# afron_atmega328_chassis.net
KiCad netlist of a schematic drawn in EAGLE
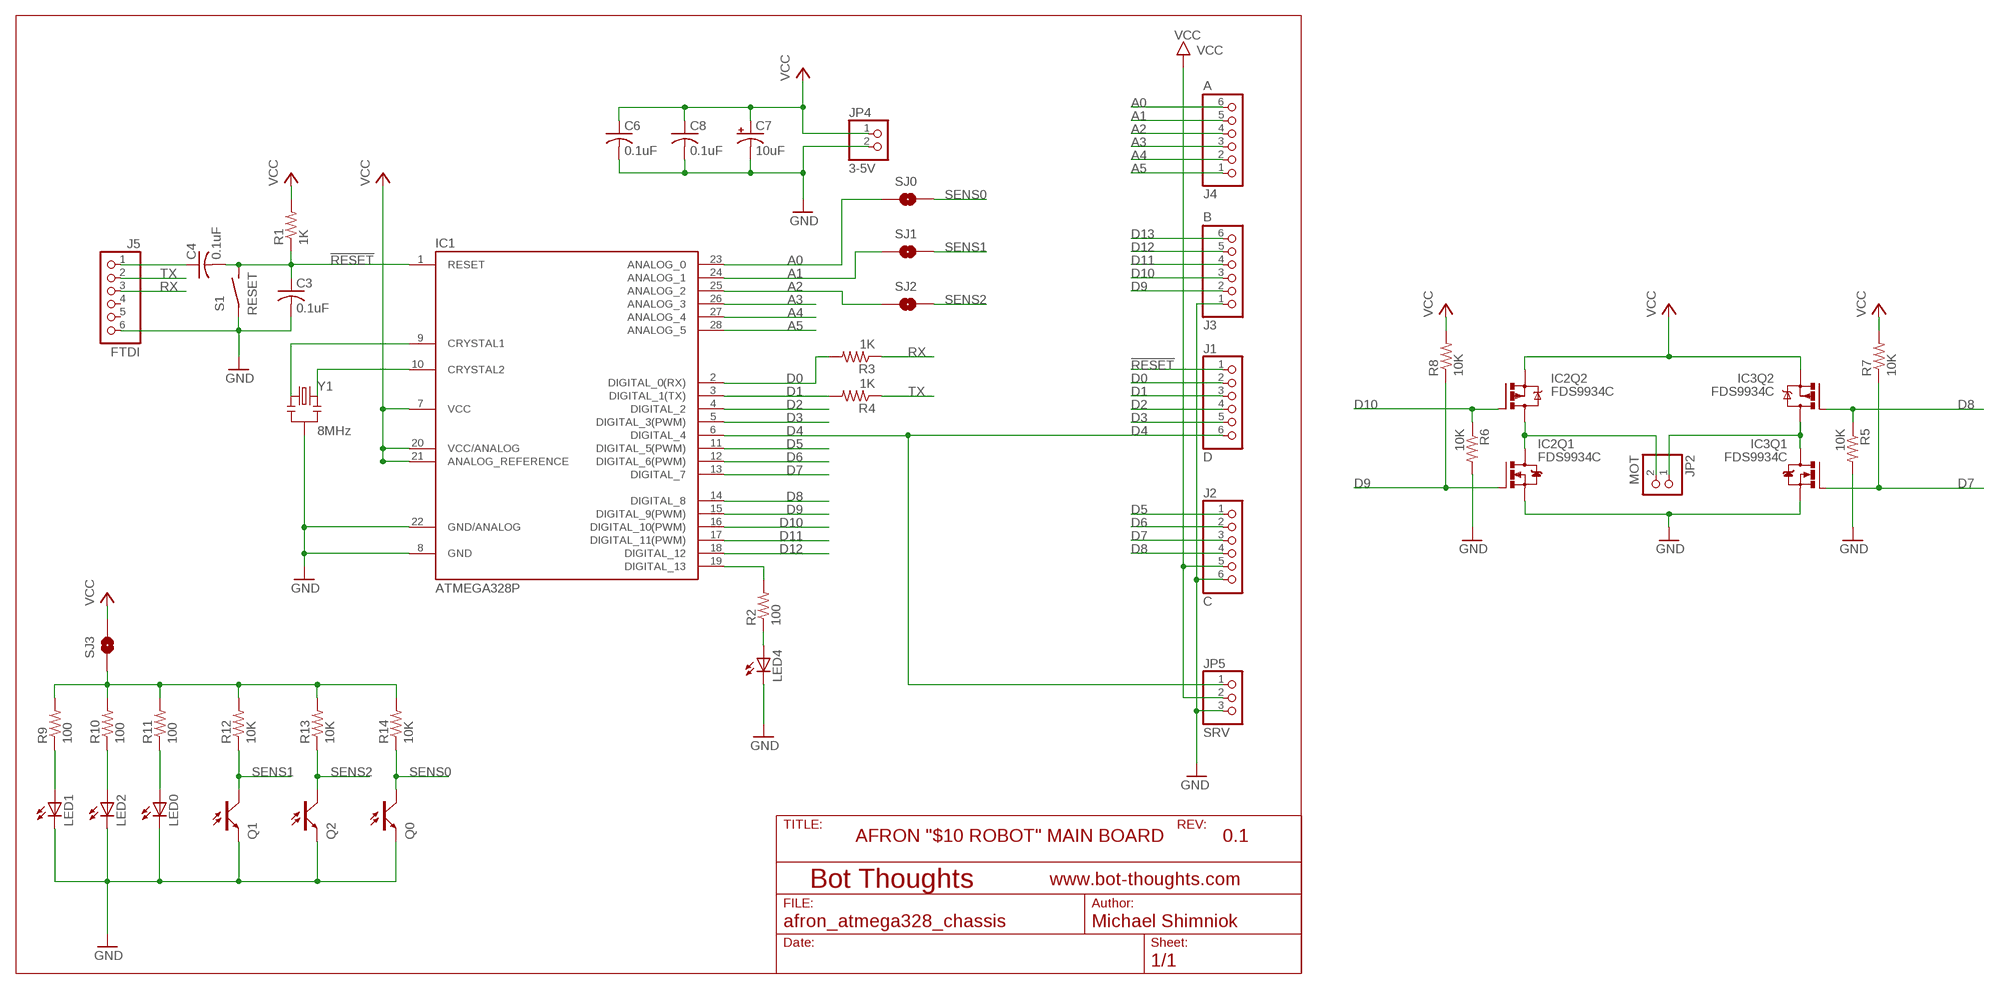
[diagram p0: schematic, sheet 1]

(export (version "E")
  (design (tool "Eeschema 10.0.6"))
  (components
    (comp (ref "C3")
      (value "0.1uF")
      (footprint "eagle-import:C050-024X044")
      (libsource (lib "eagle-import") (part "C-US050-024X044"))
    )
    (comp (ref "C4")
      (value "0.1uF")
      (footprint "eagle-import:C050-024X044")
      (libsource (lib "eagle-import") (part "C-US050-024X044"))
    )
    (comp (ref "C6")
      (value "0.1uF")
      (footprint "eagle-import:C050-024X044")
      (libsource (lib "eagle-import") (part "C-US050-024X044"))
    )
    (comp (ref "C7")
      (value "10uF")
      (footprint "eagle-import:E2,5-6")
      (libsource (lib "eagle-import") (part "CPOL-USE2.5-6"))
    )
    (comp (ref "C8")
      (value "0.1uF")
      (footprint "eagle-import:C050-024X044")
      (libsource (lib "eagle-import") (part "C-US050-024X044"))
    )
    (comp (ref "IC1")
      (value "ATMEGA328P")
      (footprint "eagle-import:DIL28-3")
      (libsource (lib "eagle-import") (part "ATMEGA168-PU"))
    )
    (comp (ref "IC2")
      (value "FDS9934C")
      (footprint "eagle-import:SOIC8")
      (libsource (lib "eagle-import") (part "FDS9934C"))
    )
    (comp (ref "IC3")
      (value "FDS9934C")
      (footprint "eagle-import:SOIC8")
      (libsource (lib "eagle-import") (part "FDS9934C"))
    )
    (comp (ref "J1")
      (value "D")
      (footprint "eagle-import:1X06-S")
      (libsource (lib "eagle-import") (part "PINHD-1X06_2.54-S"))
    )
    (comp (ref "J2")
      (value "C")
      (footprint "eagle-import:1X06-S")
      (libsource (lib "eagle-import") (part "PINHD-1X06_2.54-S"))
    )
    (comp (ref "J3")
      (value "B")
      (footprint "eagle-import:1X06-S")
      (libsource (lib "eagle-import") (part "PINHD-1X06_2.54-S"))
    )
    (comp (ref "J4")
      (value "A")
      (footprint "eagle-import:1X06-S")
      (libsource (lib "eagle-import") (part "PINHD-1X06_2.54-S"))
    )
    (comp (ref "J5")
      (value "FTDI")
      (footprint "eagle-import:1X06-S")
      (libsource (lib "eagle-import") (part "PINHD-1X06_2.54-S"))
    )
    (comp (ref "JP2")
      (value "MOT")
      (footprint "eagle-import:1X02-S")
      (libsource (lib "eagle-import") (part "PINHD-1X02_2.54-S"))
    )
    (comp (ref "JP4")
      (value "3-5V")
      (footprint "eagle-import:1X02-S")
      (libsource (lib "eagle-import") (part "PINHD-1X02_2.54-S"))
    )
    (comp (ref "JP5")
      (value "SRV")
      (footprint "eagle-import:1X03-S")
      (libsource (lib "eagle-import") (part "PINHD-1X03_2.54-S"))
    )
    (comp (ref "LED0")
      (value "LED3MM")
      (footprint "eagle-import:LED3MM")
      (libsource (lib "eagle-import") (part "LED3MM"))
    )
    (comp (ref "LED1")
      (value "LED3MM")
      (footprint "eagle-import:LED3MM")
      (libsource (lib "eagle-import") (part "LED3MM"))
    )
    (comp (ref "LED2")
      (value "LED3MM")
      (footprint "eagle-import:LED3MM")
      (libsource (lib "eagle-import") (part "LED3MM"))
    )
    (comp (ref "LED4")
      (value "LED3MM")
      (footprint "eagle-import:LED3MM")
      (libsource (lib "eagle-import") (part "LED3MM"))
    )
    (comp (ref "Q0")
      (value "PHOTOTRANSISTOR3MM")
      (footprint "eagle-import:LED3MM")
      (libsource (lib "eagle-import") (part "PHOTOTRANSISTOR3MM"))
    )
    (comp (ref "Q1")
      (value "PHOTOTRANSISTOR3MM")
      (footprint "eagle-import:LED3MM")
      (libsource (lib "eagle-import") (part "PHOTOTRANSISTOR3MM"))
    )
    (comp (ref "Q2")
      (value "PHOTOTRANSISTOR3MM")
      (footprint "eagle-import:LED3MM")
      (libsource (lib "eagle-import") (part "PHOTOTRANSISTOR3MM"))
    )
    (comp (ref "R1")
      (value "1K")
      (footprint "eagle-import:0204_5")
      (libsource (lib "eagle-import") (part "R-US_0204/5"))
    )
    (comp (ref "R2")
      (value "100")
      (footprint "eagle-import:0204_5")
      (libsource (lib "eagle-import") (part "R-US_0204/5"))
    )
    (comp (ref "R3")
      (value "1K")
      (footprint "eagle-import:0204_5")
      (libsource (lib "eagle-import") (part "R-US_0204/5"))
    )
    (comp (ref "R4")
      (value "1K")
      (footprint "eagle-import:0204_5")
      (libsource (lib "eagle-import") (part "R-US_0204/5"))
    )
    (comp (ref "R5")
      (value "10K")
      (footprint "eagle-import:0204_5")
      (libsource (lib "eagle-import") (part "R-US_0204/5"))
    )
    (comp (ref "R6")
      (value "10K")
      (footprint "eagle-import:0204_5")
      (libsource (lib "eagle-import") (part "R-US_0204/5"))
    )
    (comp (ref "R7")
      (value "10K")
      (footprint "eagle-import:0204_5")
      (libsource (lib "eagle-import") (part "R-US_0204/5"))
    )
    (comp (ref "R8")
      (value "10K")
      (footprint "eagle-import:0204_5")
      (libsource (lib "eagle-import") (part "R-US_0204/5"))
    )
    (comp (ref "R9")
      (value "100")
      (footprint "eagle-import:0204_5")
      (libsource (lib "eagle-import") (part "R-US_0204/5"))
    )
    (comp (ref "R10")
      (value "100")
      (footprint "eagle-import:0204_5")
      (libsource (lib "eagle-import") (part "R-US_0204/5"))
    )
    (comp (ref "R11")
      (value "100")
      (footprint "eagle-import:0204_5")
      (libsource (lib "eagle-import") (part "R-US_0204/5"))
    )
    (comp (ref "R12")
      (value "10K")
      (footprint "eagle-import:0204_5")
      (libsource (lib "eagle-import") (part "R-US_0204/5"))
    )
    (comp (ref "R13")
      (value "10K")
      (footprint "eagle-import:0204_5")
      (libsource (lib "eagle-import") (part "R-US_0204/5"))
    )
    (comp (ref "R14")
      (value "10K")
      (footprint "eagle-import:0204_5")
      (libsource (lib "eagle-import") (part "R-US_0204/5"))
    )
    (comp (ref "S1")
      (value "RESET")
      (footprint "eagle-import:6MMTACTILE")
      (libsource (lib "eagle-import") (part "SPST_TACT2"))
    )
    (comp (ref "SJ0")
      (value "SOLDERJUMPERTRACE")
      (footprint "eagle-import:SJ_2S-TRACE")
      (libsource (lib "eagle-import") (part "SOLDERJUMPERTRACE"))
    )
    (comp (ref "SJ1")
      (value "SOLDERJUMPERTRACE")
      (footprint "eagle-import:SJ_2S-TRACE")
      (libsource (lib "eagle-import") (part "SOLDERJUMPERTRACE"))
    )
    (comp (ref "SJ2")
      (value "SOLDERJUMPERTRACE")
      (footprint "eagle-import:SJ_2S-TRACE")
      (libsource (lib "eagle-import") (part "SOLDERJUMPERTRACE"))
    )
    (comp (ref "SJ3")
      (value "SOLDERJUMPERTRACE")
      (footprint "eagle-import:SJ_2S-TRACE")
      (libsource (lib "eagle-import") (part "SOLDERJUMPERTRACE"))
    )
    (comp (ref "Y1")
      (value "8MHz")
      (footprint "eagle-import:RESONATOR-PTH")
      (libsource (lib "eagle-import") (part "RESONATORPTH"))
    )
  )
  (nets
    (net (code "1") (name "/A0") (class "Default")
      (node (ref "IC1") (pin "23") (pinfunction "ANALOG_0_23") (pintype "bidirectional"))
      (node (ref "J4") (pin "6") (pinfunction "6_6") (pintype "passive"))
      (node (ref "SJ0") (pin "1") (pinfunction "1_1") (pintype "passive"))
    )
    (net (code "2") (name "/A1") (class "Default")
      (node (ref "IC1") (pin "24") (pinfunction "ANALOG_1_24") (pintype "bidirectional"))
      (node (ref "J4") (pin "5") (pinfunction "5_5") (pintype "passive"))
      (node (ref "SJ1") (pin "1") (pinfunction "1_1") (pintype "passive"))
    )
    (net (code "3") (name "/A2") (class "Default")
      (node (ref "IC1") (pin "25") (pinfunction "ANALOG_2_25") (pintype "bidirectional"))
      (node (ref "J4") (pin "4") (pinfunction "4_4") (pintype "passive"))
      (node (ref "SJ2") (pin "1") (pinfunction "1_1") (pintype "passive"))
    )
    (net (code "4") (name "/A3") (class "Default")
      (node (ref "IC1") (pin "26") (pinfunction "ANALOG_3_26") (pintype "bidirectional"))
      (node (ref "J4") (pin "3") (pinfunction "3_3") (pintype "passive"))
    )
    (net (code "5") (name "/A4") (class "Default")
      (node (ref "IC1") (pin "27") (pinfunction "ANALOG_4_27") (pintype "bidirectional"))
      (node (ref "J4") (pin "2") (pinfunction "2_2") (pintype "passive"))
    )
    (net (code "6") (name "/A5") (class "Default")
      (node (ref "IC1") (pin "28") (pinfunction "ANALOG_5_28") (pintype "bidirectional"))
      (node (ref "J4") (pin "1") (pinfunction "1_1") (pintype "passive"))
    )
    (net (code "7") (name "/D0") (class "Default")
      (node (ref "IC1") (pin "2") (pinfunction "DIGITAL_0(RX)_2") (pintype "bidirectional"))
      (node (ref "J1") (pin "2") (pinfunction "2_2") (pintype "passive"))
      (node (ref "R3") (pin "2") (pinfunction "2_2") (pintype "passive"))
    )
    (net (code "8") (name "/D1") (class "Default")
      (node (ref "IC1") (pin "3") (pinfunction "DIGITAL_1(TX)_3") (pintype "bidirectional"))
      (node (ref "J1") (pin "3") (pinfunction "3_3") (pintype "passive"))
      (node (ref "R4") (pin "2") (pinfunction "2_2") (pintype "passive"))
    )
    (net (code "9") (name "/D2") (class "Default")
      (node (ref "IC1") (pin "4") (pinfunction "DIGITAL_2_4") (pintype "bidirectional"))
      (node (ref "J1") (pin "4") (pinfunction "4_4") (pintype "passive"))
    )
    (net (code "10") (name "/D3") (class "Default")
      (node (ref "IC1") (pin "5") (pinfunction "DIGITAL_3(PWM)_5") (pintype "bidirectional"))
      (node (ref "J1") (pin "5") (pinfunction "5_5") (pintype "passive"))
    )
    (net (code "11") (name "/D4") (class "Default")
      (node (ref "IC1") (pin "6") (pinfunction "DIGITAL_4_6") (pintype "bidirectional"))
      (node (ref "J1") (pin "6") (pinfunction "6_6") (pintype "passive"))
      (node (ref "JP5") (pin "1") (pinfunction "1_1") (pintype "passive"))
    )
    (net (code "12") (name "/D5") (class "Default")
      (node (ref "IC1") (pin "11") (pinfunction "DIGITAL_5(PWM)_11") (pintype "bidirectional"))
      (node (ref "J2") (pin "1") (pinfunction "1_1") (pintype "passive"))
    )
    (net (code "13") (name "/D6") (class "Default")
      (node (ref "IC1") (pin "12") (pinfunction "DIGITAL_6(PWM)_12") (pintype "bidirectional"))
      (node (ref "J2") (pin "2") (pinfunction "2_2") (pintype "passive"))
    )
    (net (code "14") (name "/D7") (class "Default")
      (node (ref "IC1") (pin "13") (pinfunction "DIGITAL_7_13") (pintype "bidirectional"))
      (node (ref "IC3") (pin "2") (pinfunction "G_2") (pintype "passive"))
      (node (ref "J2") (pin "3") (pinfunction "3_3") (pintype "passive"))
      (node (ref "R7") (pin "1") (pinfunction "1_1") (pintype "passive"))
    )
    (net (code "15") (name "/D8") (class "Default")
      (node (ref "IC1") (pin "14") (pinfunction "DIGITAL_8_14") (pintype "bidirectional"))
      (node (ref "IC3") (pin "4") (pinfunction "G_4") (pintype "passive"))
      (node (ref "J2") (pin "4") (pinfunction "4_4") (pintype "passive"))
      (node (ref "R5") (pin "1") (pinfunction "1_1") (pintype "passive"))
    )
    (net (code "16") (name "/D9") (class "Default")
      (node (ref "IC1") (pin "15") (pinfunction "DIGITAL_9(PWM)_15") (pintype "bidirectional"))
      (node (ref "IC2") (pin "2") (pinfunction "G_2") (pintype "passive"))
      (node (ref "J3") (pin "2") (pinfunction "2_2") (pintype "passive"))
      (node (ref "R8") (pin "1") (pinfunction "1_1") (pintype "passive"))
    )
    (net (code "17") (name "/D10") (class "Default")
      (node (ref "IC1") (pin "16") (pinfunction "DIGITAL_10(PWM)_16") (pintype "bidirectional"))
      (node (ref "IC2") (pin "4") (pinfunction "G_4") (pintype "passive"))
      (node (ref "J3") (pin "3") (pinfunction "3_3") (pintype "passive"))
      (node (ref "R6") (pin "1") (pinfunction "1_1") (pintype "passive"))
    )
    (net (code "18") (name "/D11") (class "Default")
      (node (ref "IC1") (pin "17") (pinfunction "DIGITAL_11(PWM)_17") (pintype "bidirectional"))
      (node (ref "J3") (pin "4") (pinfunction "4_4") (pintype "passive"))
    )
    (net (code "19") (name "/D12") (class "Default")
      (node (ref "IC1") (pin "18") (pinfunction "DIGITAL_12_18") (pintype "bidirectional"))
      (node (ref "J3") (pin "5") (pinfunction "5_5") (pintype "passive"))
    )
    (net (code "20") (name "/D13") (class "Default")
      (node (ref "IC1") (pin "19") (pinfunction "DIGITAL_13_19") (pintype "bidirectional"))
      (node (ref "J3") (pin "6") (pinfunction "6_6") (pintype "passive"))
      (node (ref "R2") (pin "2") (pinfunction "2_2") (pintype "passive"))
    )
    (net (code "21") (name "/RX") (class "Default")
      (node (ref "J5") (pin "3") (pinfunction "3_3") (pintype "passive"))
      (node (ref "R3") (pin "1") (pinfunction "1_1") (pintype "passive"))
    )
    (net (code "22") (name "/SENS0") (class "Default")
      (node (ref "Q0") (pin "A") (pinfunction "A_A") (pintype "passive"))
      (node (ref "R14") (pin "1") (pinfunction "1_1") (pintype "passive"))
      (node (ref "SJ0") (pin "2") (pinfunction "2_2") (pintype "passive"))
    )
    (net (code "23") (name "/SENS1") (class "Default")
      (node (ref "Q1") (pin "A") (pinfunction "A_A") (pintype "passive"))
      (node (ref "R12") (pin "1") (pinfunction "1_1") (pintype "passive"))
      (node (ref "SJ1") (pin "2") (pinfunction "2_2") (pintype "passive"))
    )
    (net (code "24") (name "/SENS2") (class "Default")
      (node (ref "Q2") (pin "A") (pinfunction "A_A") (pintype "passive"))
      (node (ref "R13") (pin "1") (pinfunction "1_1") (pintype "passive"))
      (node (ref "SJ2") (pin "2") (pinfunction "2_2") (pintype "passive"))
    )
    (net (code "25") (name "/TX") (class "Default")
      (node (ref "J5") (pin "2") (pinfunction "2_2") (pintype "passive"))
      (node (ref "R4") (pin "1") (pinfunction "1_1") (pintype "passive"))
    )
    (net (code "26") (name "/~{RESET}") (class "Default")
      (node (ref "C3") (pin "1") (pinfunction "1_1") (pintype "passive"))
      (node (ref "C4") (pin "2") (pinfunction "2_2") (pintype "passive"))
      (node (ref "IC1") (pin "1") (pinfunction "RESET_1") (pintype "bidirectional"))
      (node (ref "J1") (pin "1") (pinfunction "1_1") (pintype "passive"))
      (node (ref "R1") (pin "1") (pinfunction "1_1") (pintype "passive"))
      (node (ref "S1") (pin "P$2") (pinfunction "S_P$2") (pintype "passive"))
    )
    (net (code "27") (name "GND") (class "Default")
      (node (ref "C3") (pin "2") (pinfunction "2_2") (pintype "passive"))
      (node (ref "C6") (pin "2") (pinfunction "2_2") (pintype "passive"))
      (node (ref "C7") (pin "-") (pinfunction "-_-") (pintype "passive"))
      (node (ref "C8") (pin "2") (pinfunction "2_2") (pintype "passive"))
      (node (ref "IC1") (pin "22") (pinfunction "GND/ANALOG_22") (pintype "power_in"))
      (node (ref "IC1") (pin "8") (pinfunction "GND_8") (pintype "power_in"))
      (node (ref "IC2") (pin "1") (pinfunction "S_1") (pintype "passive"))
      (node (ref "IC3") (pin "1") (pinfunction "S_1") (pintype "passive"))
      (node (ref "J2") (pin "6") (pinfunction "6_6") (pintype "passive"))
      (node (ref "J3") (pin "1") (pinfunction "1_1") (pintype "passive"))
      (node (ref "J5") (pin "6") (pinfunction "6_6") (pintype "passive"))
      (node (ref "JP4") (pin "2") (pinfunction "2_2") (pintype "passive"))
      (node (ref "JP5") (pin "3") (pinfunction "3_3") (pintype "passive"))
      (node (ref "LED0") (pin "K") (pinfunction "C_K") (pintype "passive"))
      (node (ref "LED1") (pin "K") (pinfunction "C_K") (pintype "passive"))
      (node (ref "LED2") (pin "K") (pinfunction "C_K") (pintype "passive"))
      (node (ref "LED4") (pin "K") (pinfunction "C_K") (pintype "passive"))
      (node (ref "Q0") (pin "K") (pinfunction "C_K") (pintype "passive"))
      (node (ref "Q1") (pin "K") (pinfunction "C_K") (pintype "passive"))
      (node (ref "Q2") (pin "K") (pinfunction "C_K") (pintype "passive"))
      (node (ref "R5") (pin "2") (pinfunction "2_2") (pintype "passive"))
      (node (ref "R6") (pin "2") (pinfunction "2_2") (pintype "passive"))
      (node (ref "S1") (pin "P$1") (pinfunction "P_P$1") (pintype "passive"))
      (node (ref "Y1") (pin "2") (pinfunction "2_2") (pintype "passive"))
    )
    (net (code "28") (name "Net-(C4-Pad1)") (class "Default")
      (node (ref "C4") (pin "1") (pinfunction "1_1") (pintype "passive"))
      (node (ref "J5") (pin "1") (pinfunction "1_1") (pintype "passive"))
    )
    (net (code "29") (name "Net-(IC1-CRYSTAL1)") (class "Default")
      (node (ref "IC1") (pin "9") (pinfunction "CRYSTAL1_9") (pintype "bidirectional"))
      (node (ref "Y1") (pin "1") (pinfunction "1_1") (pintype "passive"))
    )
    (net (code "30") (name "Net-(IC1-CRYSTAL2)") (class "Default")
      (node (ref "IC1") (pin "10") (pinfunction "CRYSTAL2_10") (pintype "bidirectional"))
      (node (ref "Y1") (pin "3") (pinfunction "3_3") (pintype "passive"))
    )
    (net (code "31") (name "Net-(IC2A-D-Pad7)") (class "Default")
      (node (ref "IC2") (pin "5") (pinfunction "D_5") (pintype "passive"))
      (node (ref "IC2") (pin "6") (pinfunction "D_6") (pintype "passive"))
      (node (ref "IC2") (pin "7") (pinfunction "D_7") (pintype "passive"))
      (node (ref "IC2") (pin "8") (pinfunction "D_8") (pintype "passive"))
      (node (ref "JP2") (pin "2") (pinfunction "2_2") (pintype "passive"))
    )
    (net (code "32") (name "Net-(IC3A-D-Pad7)") (class "Default")
      (node (ref "IC3") (pin "5") (pinfunction "D_5") (pintype "passive"))
      (node (ref "IC3") (pin "6") (pinfunction "D_6") (pintype "passive"))
      (node (ref "IC3") (pin "7") (pinfunction "D_7") (pintype "passive"))
      (node (ref "IC3") (pin "8") (pinfunction "D_8") (pintype "passive"))
      (node (ref "JP2") (pin "1") (pinfunction "1_1") (pintype "passive"))
    )
    (net (code "33") (name "Net-(LED0-PadA)") (class "Default")
      (node (ref "LED0") (pin "A") (pinfunction "A_A") (pintype "passive"))
      (node (ref "R11") (pin "1") (pinfunction "1_1") (pintype "passive"))
    )
    (net (code "34") (name "Net-(LED1-PadA)") (class "Default")
      (node (ref "LED1") (pin "A") (pinfunction "A_A") (pintype "passive"))
      (node (ref "R9") (pin "1") (pinfunction "1_1") (pintype "passive"))
    )
    (net (code "35") (name "Net-(LED2-PadA)") (class "Default")
      (node (ref "LED2") (pin "A") (pinfunction "A_A") (pintype "passive"))
      (node (ref "R10") (pin "1") (pinfunction "1_1") (pintype "passive"))
    )
    (net (code "36") (name "Net-(LED4-PadA)") (class "Default")
      (node (ref "LED4") (pin "A") (pinfunction "A_A") (pintype "passive"))
      (node (ref "R2") (pin "1") (pinfunction "1_1") (pintype "passive"))
    )
    (net (code "37") (name "Net-(R10-Pad2)") (class "Default")
      (node (ref "R10") (pin "2") (pinfunction "2_2") (pintype "passive"))
      (node (ref "R11") (pin "2") (pinfunction "2_2") (pintype "passive"))
      (node (ref "R12") (pin "2") (pinfunction "2_2") (pintype "passive"))
      (node (ref "R13") (pin "2") (pinfunction "2_2") (pintype "passive"))
      (node (ref "R14") (pin "2") (pinfunction "2_2") (pintype "passive"))
      (node (ref "R9") (pin "2") (pinfunction "2_2") (pintype "passive"))
      (node (ref "SJ3") (pin "1") (pinfunction "1_1") (pintype "passive"))
    )
    (net (code "38") (name "VCC") (class "Default")
      (node (ref "C6") (pin "1") (pinfunction "1_1") (pintype "passive"))
      (node (ref "C7") (pin "+") (pinfunction "+_+") (pintype "passive"))
      (node (ref "C8") (pin "1") (pinfunction "1_1") (pintype "passive"))
      (node (ref "IC1") (pin "20") (pinfunction "VCC/ANALOG_20") (pintype "passive"))
      (node (ref "IC1") (pin "21") (pinfunction "ANALOG_REFERENCE_21") (pintype "passive"))
      (node (ref "IC1") (pin "7") (pinfunction "VCC_7") (pintype "power_in"))
      (node (ref "IC2") (pin "3") (pinfunction "S_3") (pintype "passive"))
      (node (ref "IC3") (pin "3") (pinfunction "S_3") (pintype "passive"))
      (node (ref "J2") (pin "5") (pinfunction "5_5") (pintype "passive"))
      (node (ref "JP4") (pin "1") (pinfunction "1_1") (pintype "passive"))
      (node (ref "JP5") (pin "2") (pinfunction "2_2") (pintype "passive"))
      (node (ref "R1") (pin "2") (pinfunction "2_2") (pintype "passive"))
      (node (ref "R7") (pin "2") (pinfunction "2_2") (pintype "passive"))
      (node (ref "R8") (pin "2") (pinfunction "2_2") (pintype "passive"))
      (node (ref "SJ3") (pin "2") (pinfunction "2_2") (pintype "passive"))
    )
    (net (code "39") (name "unconnected-(J5-Pad4)") (class "Default")
      (node (ref "J5") (pin "4") (pinfunction "4_4") (pintype "passive"))
    )
    (net (code "40") (name "unconnected-(J5-Pad5)") (class "Default")
      (node (ref "J5") (pin "5") (pinfunction "5_5") (pintype "passive"))
    )
  )
)
